# Ball_Locator_Andre_Seidel_Oliveira_s_con.net
KiCad netlist of a schematic drawn in Altium Designer
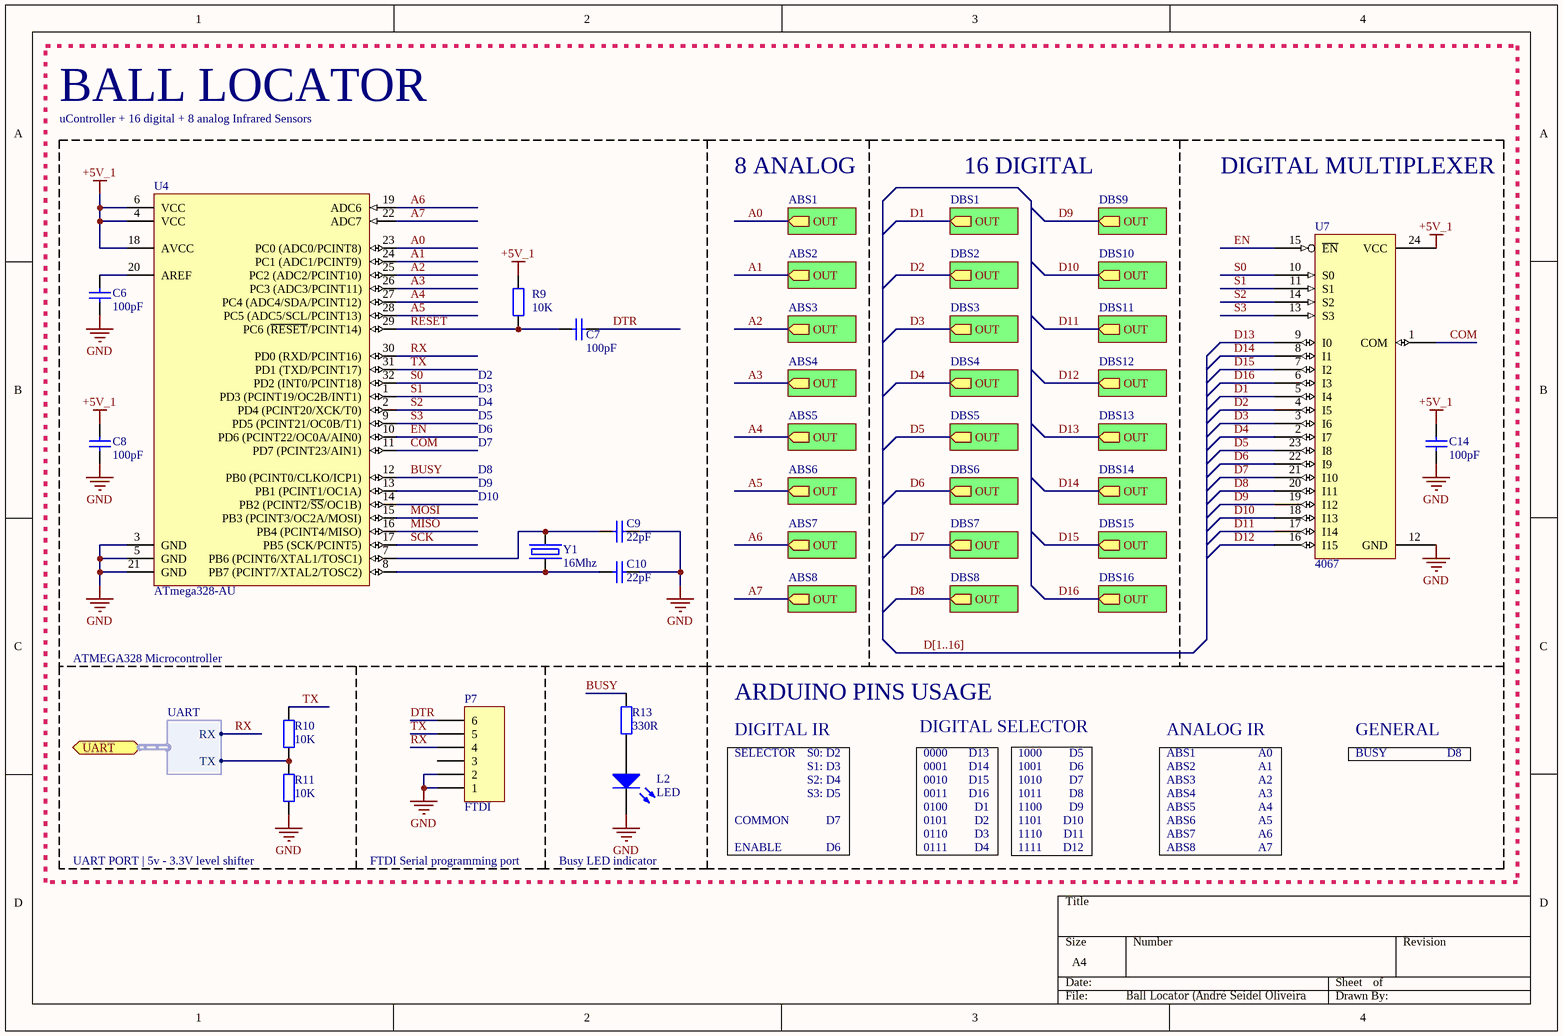
[diagram p0: Ball Locator (André Seidel Oliveira's conflicted copy 2013-01-27).SchDoc]

(export (version "E")
  (design (tool "Eeschema 10.0.6"))
  (components
    (comp (ref "C6")
      (value "100pF")
      (footprint "6-0805_N")
      (description "Capacitor (Semiconductor SIM Model)")
      (fields (field (name "Comment") "Cap Semi") (field (name "PUBLISHER") "Altium Limited"))
      (libsource (lib "Miscellaneous Devices") (part "Cap Semi"))
    )
    (comp (ref "C7")
      (value "100pF")
      (footprint "6-0805_N")
      (description "Capacitor (Semiconductor SIM Model)")
      (fields (field (name "Comment") "Cap Semi") (field (name "PUBLISHER") "Altium Limited"))
      (libsource (lib "Miscellaneous Devices") (part "Cap Semi"))
    )
    (comp (ref "C8")
      (value "100pF")
      (footprint "6-0805_N")
      (description "Capacitor (Semiconductor SIM Model)")
      (fields (field (name "Comment") "Cap Semi") (field (name "PUBLISHER") "Altium Limited"))
      (libsource (lib "Miscellaneous Devices") (part "Cap Semi"))
    )
    (comp (ref "C9")
      (value "22pF")
      (footprint "6-0805_N")
      (description "Capacitor (Semiconductor SIM Model)")
      (fields (field (name "Comment") "Cap Semi") (field (name "PUBLISHER") "Altium Limited"))
      (libsource (lib "Miscellaneous Devices") (part "Cap Semi"))
    )
    (comp (ref "C10")
      (value "22pF")
      (footprint "6-0805_N")
      (description "Capacitor (Semiconductor SIM Model)")
      (fields (field (name "Comment") "Cap Semi") (field (name "PUBLISHER") "Altium Limited"))
      (libsource (lib "Miscellaneous Devices") (part "Cap Semi"))
    )
    (comp (ref "C14")
      (value "100pF")
      (footprint "6-0805_N")
      (description "Capacitor (Semiconductor SIM Model)")
      (fields (field (name "Comment") "Cap Semi") (field (name "PUBLISHER") "Altium Limited"))
      (libsource (lib "Miscellaneous Devices") (part "Cap Semi"))
    )
    (comp (ref "L2") (value "LED") (footprint "LED0805") (libsource (lib "CustomLibrary") (part "LED")))
    (comp (ref "P7")
      (value "FTDI")
      (footprint "HDR1X6")
      (description "Header, 6-Pin")
      (fields (field (name "PUBLISHER") "Altium Limited"))
      (libsource (lib "Miscellaneous Connectors") (part "Header 6"))
    )
    (comp (ref "R9") (value "10K") (footprint "RES1206") (libsource (lib "") (part "RES_1")))
    (comp (ref "R10") (value "10K") (footprint "RES1206") (libsource (lib "CustomLibrary") (part "RES")))
    (comp (ref "R11") (value "10K") (footprint "RES1206") (libsource (lib "CustomLibrary") (part "RES")))
    (comp (ref "R13") (value "330R") (footprint "RES1206") (libsource (lib "CustomLibrary") (part "RES")))
    (comp (ref "U4")
      (value "ATmega328-AU")
      (footprint "32A_N")
      (fields (field (name "PUBLISHER") "Altium Limited"))
      (libsource (lib "Atmel Microcontroller 8-Bit megaAVR") (part "ATmega328-AU"))
    )
    (comp (ref "U7")
      (value "4067")
      (footprint "SSOP-24")
      (description "MUX-74HC4067")
      (libsource (lib "CustomLibrary") (part "MUX-74HC4067"))
    )
    (comp (ref "Y1")
      (value "16Mhz")
      (footprint "OSC-2-PIN-TH")
      (description "2 pin oscilator")
      (libsource (lib "CustomLibrary") (part "OSC-2-PIN"))
    )
  )
  (nets
    (net (code "2") (name "+5V_1") (class "Default")
      (node (ref "C14") (pin "2") (pinfunction "2_2") (pintype "passive"))
      (node (ref "C8") (pin "2") (pinfunction "2_2") (pintype "passive"))
      (node (ref "R9") (pin "1") (pinfunction "1_1") (pintype "passive"))
      (node (ref "U4") (pin "18") (pinfunction "AVCC_18") (pintype "power_in"))
      (node (ref "U4") (pin "4") (pinfunction "VCC_4") (pintype "power_in"))
      (node (ref "U4") (pin "6") (pinfunction "VCC_6") (pintype "power_in"))
      (node (ref "U7") (pin "24") (pinfunction "VCC_24") (pintype "power_in"))
    )
    (net (code "3") (name "/A0") (class "Default")
      (node (ref "U4") (pin "23") (pinfunction "PC0_(ADC0/PCINT8)_23") (pintype "bidirectional"))
    )
    (net (code "4") (name "/A1") (class "Default")
      (node (ref "U4") (pin "24") (pinfunction "PC1_(ADC1/PCINT9)_24") (pintype "bidirectional"))
    )
    (net (code "5") (name "/A2") (class "Default")
      (node (ref "U4") (pin "25") (pinfunction "PC2_(ADC2/PCINT10)_25") (pintype "bidirectional"))
    )
    (net (code "6") (name "/A3") (class "Default")
      (node (ref "U4") (pin "26") (pinfunction "PC3_(ADC3/PCINT11)_26") (pintype "bidirectional"))
    )
    (net (code "7") (name "/A4") (class "Default")
      (node (ref "U4") (pin "27") (pinfunction "PC4_(ADC4/SDA/PCINT12)_27") (pintype "bidirectional"))
    )
    (net (code "8") (name "/A5") (class "Default")
      (node (ref "U4") (pin "28") (pinfunction "PC5_(ADC5/SCL/PCINT13)_28") (pintype "bidirectional"))
    )
    (net (code "9") (name "/A6") (class "Default")
      (node (ref "U4") (pin "19") (pinfunction "ADC6_19") (pintype "input"))
    )
    (net (code "10") (name "/A7") (class "Default")
      (node (ref "U4") (pin "22") (pinfunction "ADC7_22") (pintype "input"))
    )
    (net (code "11") (name "/BUSY") (class "Default")
      (node (ref "R13") (pin "2") (pinfunction "2_2") (pintype "passive"))
      (node (ref "U4") (pin "12") (pinfunction "PB0_(PCINT0/CLKO/ICP1)_12") (pintype "bidirectional"))
    )
    (net (code "12") (name "/COM") (class "Default")
      (node (ref "U4") (pin "11") (pinfunction "PD7_(PCINT23/AIN1)_11") (pintype "bidirectional"))
      (node (ref "U7") (pin "1") (pinfunction "COM_1") (pintype "bidirectional"))
    )
    (net (code "13") (name "/D1") (class "Default")
      (node (ref "U7") (pin "5") (pinfunction "I4_5") (pintype "bidirectional"))
    )
    (net (code "14") (name "/D2") (class "Default")
      (node (ref "U7") (pin "4") (pinfunction "I5_4") (pintype "bidirectional"))
    )
    (net (code "15") (name "/D3") (class "Default")
      (node (ref "U7") (pin "3") (pinfunction "I6_3") (pintype "bidirectional"))
    )
    (net (code "16") (name "/D4") (class "Default")
      (node (ref "U7") (pin "2") (pinfunction "I7_2") (pintype "bidirectional"))
    )
    (net (code "17") (name "/D5") (class "Default")
      (node (ref "U7") (pin "23") (pinfunction "I8_23") (pintype "bidirectional"))
    )
    (net (code "18") (name "/D6") (class "Default")
      (node (ref "U7") (pin "22") (pinfunction "I9_22") (pintype "bidirectional"))
    )
    (net (code "19") (name "/D7") (class "Default")
      (node (ref "U7") (pin "21") (pinfunction "I10_21") (pintype "bidirectional"))
    )
    (net (code "20") (name "/D8") (class "Default")
      (node (ref "U7") (pin "20") (pinfunction "I11_20") (pintype "bidirectional"))
    )
    (net (code "21") (name "/D9") (class "Default")
      (node (ref "U7") (pin "19") (pinfunction "I12_19") (pintype "bidirectional"))
    )
    (net (code "22") (name "/D10") (class "Default")
      (node (ref "U7") (pin "18") (pinfunction "I13_18") (pintype "bidirectional"))
    )
    (net (code "23") (name "/D11") (class "Default")
      (node (ref "U7") (pin "17") (pinfunction "I14_17") (pintype "bidirectional"))
    )
    (net (code "24") (name "/D12") (class "Default")
      (node (ref "U7") (pin "16") (pinfunction "I15_16") (pintype "bidirectional"))
    )
    (net (code "25") (name "/D13") (class "Default")
      (node (ref "U7") (pin "9") (pinfunction "I0_9") (pintype "bidirectional"))
    )
    (net (code "26") (name "/D14") (class "Default")
      (node (ref "U7") (pin "8") (pinfunction "I1_8") (pintype "bidirectional"))
    )
    (net (code "27") (name "/D15") (class "Default")
      (node (ref "U7") (pin "7") (pinfunction "I2_7") (pintype "bidirectional"))
    )
    (net (code "28") (name "/D16") (class "Default")
      (node (ref "U7") (pin "6") (pinfunction "I3_6") (pintype "bidirectional"))
    )
    (net (code "29") (name "/DTR") (class "Default")
      (node (ref "C7") (pin "2") (pinfunction "2_2") (pintype "passive"))
      (node (ref "P7") (pin "6") (pinfunction "6_6") (pintype "passive"))
    )
    (net (code "31") (name "/EN") (class "Default")
      (node (ref "U4") (pin "10") (pinfunction "PD6_(PCINT22/OC0A/AIN0)_10") (pintype "bidirectional"))
      (node (ref "U7") (pin "15") (pinfunction "~{EN}_15") (pintype "input"))
    )
    (net (code "32") (name "/MISO") (class "Default")
      (node (ref "U4") (pin "16") (pinfunction "PB4_(PCINT4/MISO)_16") (pintype "bidirectional"))
    )
    (net (code "33") (name "/MOSI") (class "Default")
      (node (ref "U4") (pin "15") (pinfunction "PB3_(PCINT3/OC2A/MOSI)_15") (pintype "bidirectional"))
    )
    (net (code "34") (name "/RESET") (class "Default")
      (node (ref "C7") (pin "1") (pinfunction "1_1") (pintype "passive"))
      (node (ref "R9") (pin "2") (pinfunction "2_2") (pintype "passive"))
      (node (ref "U4") (pin "29") (pinfunction "PC6_(~{RESET}/PCINT14)_29") (pintype "bidirectional"))
    )
    (net (code "35") (name "/RX") (class "Default")
      (node (ref "P7") (pin "4") (pinfunction "4_4") (pintype "passive"))
      (node (ref "U4") (pin "30") (pinfunction "PD0_(RXD/PCINT16)_30") (pintype "bidirectional"))
    )
    (net (code "36") (name "/S0") (class "Default")
      (node (ref "U4") (pin "32") (pinfunction "PD2_(INT0/PCINT18)_32") (pintype "bidirectional"))
      (node (ref "U7") (pin "10") (pinfunction "S0_10") (pintype "input"))
    )
    (net (code "37") (name "/S1") (class "Default")
      (node (ref "U4") (pin "1") (pinfunction "PD3_(PCINT19/OC2B/INT1)_1") (pintype "bidirectional"))
      (node (ref "U7") (pin "11") (pinfunction "S1_11") (pintype "input"))
    )
    (net (code "38") (name "/S2") (class "Default")
      (node (ref "U4") (pin "2") (pinfunction "PD4_(PCINT20/XCK/T0)_2") (pintype "bidirectional"))
      (node (ref "U7") (pin "14") (pinfunction "S2_14") (pintype "input"))
    )
    (net (code "39") (name "/S3") (class "Default")
      (node (ref "U4") (pin "9") (pinfunction "PD5_(PCINT21/OC0B/T1)_9") (pintype "bidirectional"))
      (node (ref "U7") (pin "13") (pinfunction "S3_13") (pintype "input"))
    )
    (net (code "40") (name "/SCK") (class "Default")
      (node (ref "U4") (pin "17") (pinfunction "PB5_(SCK/PCINT5)_17") (pintype "bidirectional"))
    )
    (net (code "41") (name "/TX") (class "Default")
      (node (ref "P7") (pin "5") (pinfunction "5_5") (pintype "passive"))
      (node (ref "R10") (pin "2") (pinfunction "2_2") (pintype "passive"))
      (node (ref "U4") (pin "31") (pinfunction "PD1_(TXD/PCINT17)_31") (pintype "bidirectional"))
    )
    (net (code "43") (name "GND") (class "Default")
      (node (ref "C10") (pin "2") (pinfunction "2_2") (pintype "passive"))
      (node (ref "C14") (pin "1") (pinfunction "1_1") (pintype "passive"))
      (node (ref "C6") (pin "1") (pinfunction "1_1") (pintype "passive"))
      (node (ref "C8") (pin "1") (pinfunction "1_1") (pintype "passive"))
      (node (ref "C9") (pin "2") (pinfunction "2_2") (pintype "passive"))
      (node (ref "L2") (pin "2") (pinfunction "K_2") (pintype "passive"))
      (node (ref "P7") (pin "1") (pinfunction "1_1") (pintype "passive"))
      (node (ref "P7") (pin "2") (pinfunction "2_2") (pintype "passive"))
      (node (ref "R11") (pin "1") (pinfunction "1_1") (pintype "passive"))
      (node (ref "U4") (pin "21") (pinfunction "GND_21") (pintype "power_in"))
      (node (ref "U4") (pin "3") (pinfunction "GND_3") (pintype "power_in"))
      (node (ref "U4") (pin "5") (pinfunction "GND_5") (pintype "power_in"))
      (node (ref "U7") (pin "12") (pinfunction "GND_12") (pintype "power_in"))
    )
    (net (code "44") (name "Net-(L2-A)") (class "Default")
      (node (ref "L2") (pin "1") (pinfunction "A_1") (pintype "passive"))
      (node (ref "R13") (pin "1") (pinfunction "1_1") (pintype "passive"))
    )
    (net (code "45") (name "Net-(R10-Pad1)") (class "Default")
      (node (ref "R10") (pin "1") (pinfunction "1_1") (pintype "passive"))
      (node (ref "R11") (pin "2") (pinfunction "2_2") (pintype "passive"))
    )
    (net (code "46") (name "Net-(U4-AREF)") (class "Default")
      (node (ref "C6") (pin "2") (pinfunction "2_2") (pintype "passive"))
      (node (ref "U4") (pin "20") (pinfunction "AREF_20") (pintype "passive"))
    )
    (net (code "47") (name "Net-(U4-PB6_(PCINT6{slash}XTAL1{slash}TOSC1))") (class "Default")
      (node (ref "C9") (pin "1") (pinfunction "1_1") (pintype "passive"))
      (node (ref "U4") (pin "7") (pinfunction "PB6_(PCINT6/XTAL1/TOSC1)_7") (pintype "bidirectional"))
      (node (ref "Y1") (pin "1") (pinfunction "1_1") (pintype "passive"))
    )
    (net (code "48") (name "Net-(U4-PB7_(PCINT7{slash}XTAL2{slash}TOSC2))") (class "Default")
      (node (ref "C10") (pin "1") (pinfunction "1_1") (pintype "passive"))
      (node (ref "U4") (pin "8") (pinfunction "PB7_(PCINT7/XTAL2/TOSC2)_8") (pintype "bidirectional"))
      (node (ref "Y1") (pin "2") (pinfunction "2_2") (pintype "passive"))
    )
    (net (code "49") (name "unconnected-(P7-Pad3)") (class "Default")
      (node (ref "P7") (pin "3") (pinfunction "3_3") (pintype "passive"))
    )
    (net (code "50") (name "unconnected-(U4-PB1_(PCINT1{slash}OC1A)-Pad13)") (class "Default")
      (node (ref "U4") (pin "13") (pinfunction "PB1_(PCINT1/OC1A)_13") (pintype "bidirectional"))
    )
    (net (code "51") (name "unconnected-(U4-PB2_(PCINT2{slash}~{SS}{slash}OC1B)-Pad14)") (class "Default")
      (node (ref "U4") (pin "14") (pinfunction "PB2_(PCINT2/~{SS}/OC1B)_14") (pintype "bidirectional"))
    )
  )
)
